# 07_CAN_Interface.net
KiCad netlist of a schematic drawn in Altium Designer
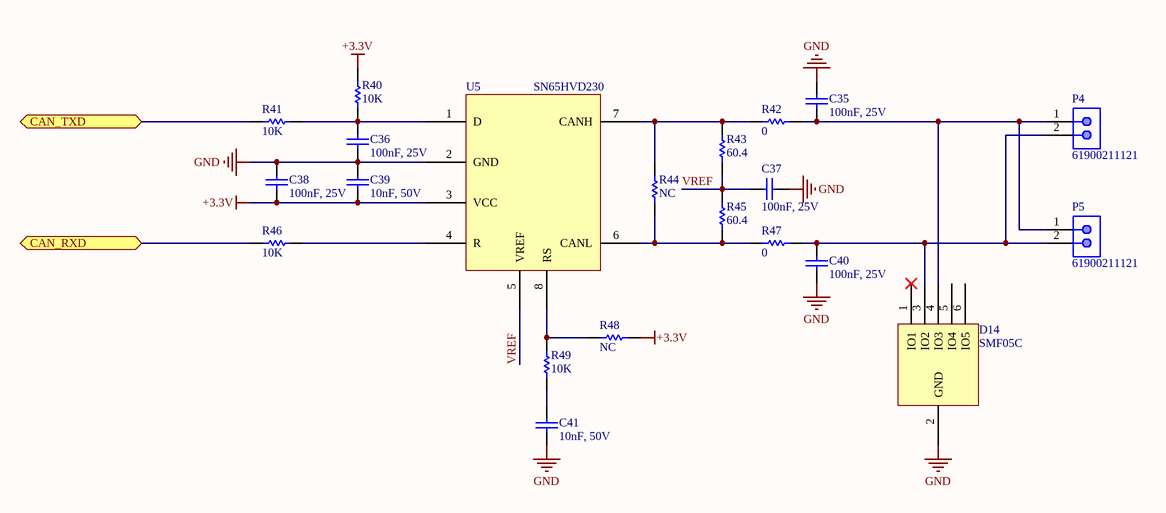
[diagram p0: 07_CAN_Interface.SchDoc]

(export (version "E")
  (design (tool "Eeschema 10.0.6"))
  (components
    (comp (ref "C35")
      (value "100nF, 25V")
      (footprint "WCAP-CSGP_0603_H=0.8mm_Reflow")
      (description "WCAP-CSGP Multilayer Ceramic Chip Capacitor, General Purpose, size 0603, X7R, 100nF, 25V")
      (fields
        (field (name "MANUFACTURER PART NUMBER") "885012206071")
        (field (name "MANUFACTURER") "Wurth Elektronik")
      )
      (libsource (lib "Altium_WCAP-CSGP (rev20a)") (part "885012206071"))
    )
    (comp (ref "C36")
      (value "100nF, 25V")
      (footprint "WCAP-CSGP_0603_H=0.8mm_Reflow")
      (description "WCAP-CSGP Multilayer Ceramic Chip Capacitor, General Purpose, size 0603, X7R, 100nF, 25V")
      (fields
        (field (name "MANUFACTURER PART NUMBER") "885012206071")
        (field (name "MANUFACTURER") "Wurth Elektronik")
      )
      (libsource (lib "Altium_WCAP-CSGP (rev20a)") (part "885012206071"))
    )
    (comp (ref "C37")
      (value "100nF, 25V")
      (footprint "WCAP-CSGP_0603_H=0.8mm_Reflow")
      (description "WCAP-CSGP Multilayer Ceramic Chip Capacitor, General Purpose, size 0603, X7R, 100nF, 25V")
      (fields
        (field (name "MANUFACTURER PART NUMBER") "885012206071")
        (field (name "MANUFACTURER") "Wurth Elektronik")
      )
      (libsource (lib "Altium_WCAP-CSGP (rev20a)") (part "885012206071"))
    )
    (comp (ref "C38")
      (value "100nF, 25V")
      (footprint "WCAP-CSGP_0603_H=0.8mm_Reflow")
      (description "WCAP-CSGP Multilayer Ceramic Chip Capacitor, General Purpose, size 0603, X7R, 100nF, 25V")
      (fields
        (field (name "MANUFACTURER PART NUMBER") "885012206071")
        (field (name "MANUFACTURER") "Wurth Elektronik")
      )
      (libsource (lib "Altium_WCAP-CSGP (rev20a)") (part "885012206071"))
    )
    (comp (ref "C39")
      (value "10nF, 50V")
      (footprint "WCAP-CSGP_0603_H=0.8mm_Reflow")
      (description "WCAP-CSGP Multilayer Ceramic Chip Capacitor, General Purpose, size 0603, X7R, 10nF, 50V")
      (fields
        (field (name "MANUFACTURER PART NUMBER") "885012206089")
        (field (name "MANUFACTURER") "Wurth Elektronik")
      )
      (libsource (lib "Altium_WCAP-CSGP (rev20a)") (part "885012206089"))
    )
    (comp (ref "C40")
      (value "100nF, 25V")
      (footprint "WCAP-CSGP_0603_H=0.8mm_Reflow")
      (description "WCAP-CSGP Multilayer Ceramic Chip Capacitor, General Purpose, size 0603, X7R, 100nF, 25V")
      (fields
        (field (name "MANUFACTURER PART NUMBER") "885012206071")
        (field (name "MANUFACTURER") "Wurth Elektronik")
      )
      (libsource (lib "Altium_WCAP-CSGP (rev20a)") (part "885012206071"))
    )
    (comp (ref "C41")
      (value "10nF, 50V")
      (footprint "WCAP-CSGP_0603_H=0.8mm_Reflow")
      (description "WCAP-CSGP Multilayer Ceramic Chip Capacitor, General Purpose, size 0603, X7R, 10nF, 50V")
      (fields
        (field (name "MANUFACTURER PART NUMBER") "885012206089")
        (field (name "MANUFACTURER") "Wurth Elektronik")
      )
      (libsource (lib "Altium_WCAP-CSGP (rev20a)") (part "885012206089"))
    )
    (comp (ref "D14")
      (value "SMF05C")
      (footprint "SOT65P210X110-6N")
      (libsource (lib "MiclsLib") (part "SMF05C"))
    )
    (comp (ref "P4")
      (value "61900211121")
      (footprint "61900211121")
      (description "WR-WTB THT Male Vertical Locking Header, pitch 2.54mm, 2p")
      (fields (field (name "PUBLISHER") "Wurth Elektronik"))
      (libsource (lib "653008114822_Altium_WR-WTB_rev20a") (part "61900211121"))
    )
    (comp (ref "P5")
      (value "61900211121")
      (footprint "61900211121")
      (description "WR-WTB THT Male Vertical Locking Header, pitch 2.54mm, 2p")
      (fields (field (name "PUBLISHER") "Wurth Elektronik"))
      (libsource (lib "653008114822_Altium_WR-WTB_rev20a") (part "61900211121"))
    )
    (comp (ref "R40")
      (value "10K")
      (footprint "RES-SM-0603")
      (description "Resistor")
      (fields (field (name "Comment") "RESISTOR SMD"))
      (libsource (lib "PIF_Library") (part "RESISTOR SMD"))
    )
    (comp (ref "R41")
      (value "10K")
      (footprint "RES-SM-0603")
      (description "Resistor")
      (fields (field (name "Comment") "RESISTOR SMD"))
      (libsource (lib "PIF_Library") (part "RESISTOR SMD"))
    )
    (comp (ref "R42")
      (value "0")
      (footprint "RES-SM-0603")
      (description "Resistor")
      (fields (field (name "Comment") "RESISTOR SMD"))
      (libsource (lib "PIF_Library") (part "RESISTOR SMD"))
    )
    (comp (ref "R43")
      (value "60.4")
      (footprint "RES-SM-0603")
      (description "Resistor")
      (fields (field (name "Comment") "RESISTOR SMD"))
      (libsource (lib "PIF_Library") (part "RESISTOR SMD"))
    )
    (comp (ref "R44")
      (value "NC")
      (footprint "RES-SM-0603")
      (description "Resistor")
      (fields (field (name "Comment") "RESISTOR SMD"))
      (libsource (lib "PIF_Library") (part "RESISTOR SMD"))
    )
    (comp (ref "R45")
      (value "60.4")
      (footprint "RES-SM-0603")
      (description "Resistor")
      (fields (field (name "Comment") "RESISTOR SMD"))
      (libsource (lib "PIF_Library") (part "RESISTOR SMD"))
    )
    (comp (ref "R46")
      (value "10K")
      (footprint "RES-SM-0603")
      (description "Resistor")
      (fields (field (name "Comment") "RESISTOR SMD"))
      (libsource (lib "PIF_Library") (part "RESISTOR SMD"))
    )
    (comp (ref "R47")
      (value "0")
      (footprint "RES-SM-0603")
      (description "Resistor")
      (fields (field (name "Comment") "RESISTOR SMD"))
      (libsource (lib "PIF_Library") (part "RESISTOR SMD"))
    )
    (comp (ref "R48")
      (value "NC")
      (footprint "RES-SM-0603")
      (description "Resistor")
      (fields (field (name "Comment") "RESISTOR SMD"))
      (libsource (lib "PIF_Library") (part "RESISTOR SMD"))
    )
    (comp (ref "R49")
      (value "10K")
      (footprint "RES-SM-0603")
      (description "Resistor")
      (fields (field (name "Comment") "RESISTOR SMD"))
      (libsource (lib "PIF_Library") (part "RESISTOR SMD"))
    )
    (comp (ref "U5")
      (value "SN65HVD230")
      (footprint "SOIC127P600X175-8N")
      (libsource (lib "MiclsLib") (part "SN65HVD230"))
    )
  )
  (nets
    (net (code "1") (name "+3.3V") (class "Default")
      (node (ref "C38") (pin "1") (pinfunction "1_1") (pintype "passive"))
      (node (ref "C39") (pin "1") (pinfunction "1_1") (pintype "passive"))
      (node (ref "R40") (pin "2") (pinfunction "2_2") (pintype "passive"))
      (node (ref "R48") (pin "1") (pinfunction "1_1") (pintype "passive"))
      (node (ref "U5") (pin "3") (pinfunction "VCC_3") (pintype "passive"))
    )
    (net (code "2") (name "/CAN_RXD") (class "Default")
      (node (ref "R46") (pin "2") (pinfunction "2_2") (pintype "passive"))
    )
    (net (code "3") (name "/CAN_TXD") (class "Default")
      (node (ref "R41") (pin "2") (pinfunction "2_2") (pintype "passive"))
    )
    (net (code "4") (name "/VREF") (class "Default")
      (node (ref "C37") (pin "2") (pinfunction "2_2") (pintype "passive"))
      (node (ref "R43") (pin "2") (pinfunction "2_2") (pintype "passive"))
      (node (ref "R45") (pin "1") (pinfunction "1_1") (pintype "passive"))
      (node (ref "U5") (pin "5") (pinfunction "VREF_5") (pintype "passive"))
    )
    (net (code "5") (name "GND") (class "Default")
      (node (ref "C35") (pin "2") (pinfunction "2_2") (pintype "passive"))
      (node (ref "C36") (pin "1") (pinfunction "1_1") (pintype "passive"))
      (node (ref "C37") (pin "1") (pinfunction "1_1") (pintype "passive"))
      (node (ref "C38") (pin "2") (pinfunction "2_2") (pintype "passive"))
      (node (ref "C39") (pin "2") (pinfunction "2_2") (pintype "passive"))
      (node (ref "C40") (pin "1") (pinfunction "1_1") (pintype "passive"))
      (node (ref "C41") (pin "1") (pinfunction "1_1") (pintype "passive"))
      (node (ref "D14") (pin "2") (pinfunction "GND_2") (pintype "passive"))
      (node (ref "U5") (pin "2") (pinfunction "GND_2") (pintype "passive"))
    )
    (net (code "6") (name "Net-(C41-Pad2)") (class "Default")
      (node (ref "C41") (pin "2") (pinfunction "2_2") (pintype "passive"))
      (node (ref "R49") (pin "1") (pinfunction "1_1") (pintype "passive"))
    )
    (net (code "7") (name "Net-(D14-IO2)") (class "Default")
      (node (ref "C40") (pin "2") (pinfunction "2_2") (pintype "passive"))
      (node (ref "D14") (pin "3") (pinfunction "IO2_3") (pintype "passive"))
      (node (ref "P4") (pin "2") (pinfunction "2_2") (pintype "passive"))
      (node (ref "P5") (pin "2") (pinfunction "2_2") (pintype "passive"))
      (node (ref "R47") (pin "1") (pinfunction "1_1") (pintype "passive"))
    )
    (net (code "8") (name "Net-(D14-IO3)") (class "Default")
      (node (ref "C35") (pin "1") (pinfunction "1_1") (pintype "passive"))
      (node (ref "D14") (pin "4") (pinfunction "IO3_4") (pintype "passive"))
      (node (ref "P4") (pin "1") (pinfunction "1_1") (pintype "passive"))
      (node (ref "P5") (pin "1") (pinfunction "1_1") (pintype "passive"))
      (node (ref "R42") (pin "1") (pinfunction "1_1") (pintype "passive"))
    )
    (net (code "9") (name "Net-(U5-CANH)") (class "Default")
      (node (ref "R42") (pin "2") (pinfunction "2_2") (pintype "passive"))
      (node (ref "R43") (pin "1") (pinfunction "1_1") (pintype "passive"))
      (node (ref "R44") (pin "1") (pinfunction "1_1") (pintype "passive"))
      (node (ref "U5") (pin "7") (pinfunction "CANH_7") (pintype "passive"))
    )
    (net (code "10") (name "Net-(U5-CANL)") (class "Default")
      (node (ref "R44") (pin "2") (pinfunction "2_2") (pintype "passive"))
      (node (ref "R45") (pin "2") (pinfunction "2_2") (pintype "passive"))
      (node (ref "R47") (pin "2") (pinfunction "2_2") (pintype "passive"))
      (node (ref "U5") (pin "6") (pinfunction "CANL_6") (pintype "passive"))
    )
    (net (code "11") (name "Net-(U5-D)") (class "Default")
      (node (ref "C36") (pin "2") (pinfunction "2_2") (pintype "passive"))
      (node (ref "R40") (pin "1") (pinfunction "1_1") (pintype "passive"))
      (node (ref "R41") (pin "1") (pinfunction "1_1") (pintype "passive"))
      (node (ref "U5") (pin "1") (pinfunction "D_1") (pintype "passive"))
    )
    (net (code "12") (name "Net-(U5-R)") (class "Default")
      (node (ref "R46") (pin "1") (pinfunction "1_1") (pintype "passive"))
      (node (ref "U5") (pin "4") (pinfunction "R_4") (pintype "passive"))
    )
    (net (code "13") (name "Net-(U5-RS)") (class "Default")
      (node (ref "R48") (pin "2") (pinfunction "2_2") (pintype "passive"))
      (node (ref "R49") (pin "2") (pinfunction "2_2") (pintype "passive"))
      (node (ref "U5") (pin "8") (pinfunction "RS_8") (pintype "passive"))
    )
    (net (code "14") (name "unconnected-(D14-IO1-Pad1)") (class "Default")
      (node (ref "D14") (pin "1") (pinfunction "IO1_1") (pintype "passive+no_connect"))
    )
    (net (code "15") (name "unconnected-(D14-IO4-Pad5)") (class "Default")
      (node (ref "D14") (pin "5") (pinfunction "IO4_5") (pintype "passive"))
    )
    (net (code "16") (name "unconnected-(D14-IO5-Pad6)") (class "Default")
      (node (ref "D14") (pin "6") (pinfunction "IO5_6") (pintype "passive"))
    )
  )
)
